# Sheet2.net
KiCad netlist of a schematic drawn in Altium Designer
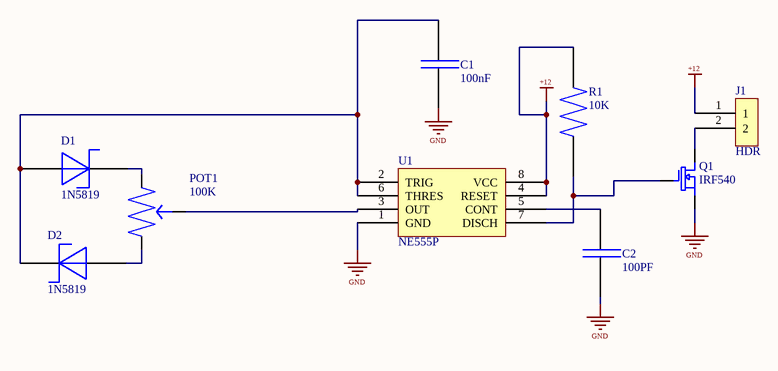
[diagram p0: Sheet2.SchDoc]

(export (version "E")
  (design (tool "Eeschema 10.0.6"))
  (components
    (comp (ref "C1")
      (value "100nF")
      (footprint "CAP")
      (description "Cap Ceramic Monolithic 0.1uF 25VDC 10% Thru-Hole Bulk")
      (fields
        (field (name "MANUFACTURER") "Murata")
        (field (name "MANUFACTURER PART NUMBER") "RCER71E104K0K1H03B")
      )
      (libsource (lib "Schlib2") (part "RCER71E104K0K1H03B"))
    )
    (comp (ref "C2")
      (value "100PF")
      (footprint "CAP")
      (fields
        (field (name "MANUFACTURER") "KEMET")
        (field (name "MANUFACTURER PART NUMBER") "C315C101F3G5TA")
      )
      (libsource (lib "Schlib2") (part "C315C101F3G5TA"))
    )
    (comp (ref "D1")
      (value "1N5819")
      (footprint "DIODE1N5819")
      (description "1N58 Series 600 mV 1 A 40 V Max Reverse Voltage Schottky Barrier Rectifier-DO-41")
      (fields (field (name "MANUFACTURER") "ON Semiconductor / Fairchild"))
      (libsource (lib "Schlib2") (part "1N5819"))
    )
    (comp (ref "D2")
      (value "1N5819")
      (footprint "DIODE1N5819")
      (description "1N58 Series 600 mV 1 A 40 V Max Reverse Voltage Schottky Barrier Rectifier-DO-41")
      (fields (field (name "MANUFACTURER") "ON Semiconductor / Fairchild"))
      (libsource (lib "Schlib2") (part "1N5819"))
    )
    (comp (ref "J1") (value "HDR") (footprint "HDR1X2") (libsource (lib "Schlib2") (part "HDR1X2")))
    (comp (ref "POT1")
      (value "100K")
      (footprint "POT")
      (description "Potentiometers 100K LINEAR 12MM")
      (fields
        (field (name "MANUFACTURER") "Bourns")
        (field (name "MANUFACTURER PART NUMBER") "PDB12-M4251-104BF")
      )
      (libsource (lib "Schlib2") (part "PDB12-M4251-104BF"))
    )
    (comp (ref "Q1")
      (value "IRF540")
      (footprint "TO-220")
      (description "MOSFET N-CH 100V 28A TO-220AB")
      (fields (field (name "MANUFACTURER") "Vishay Siliconix") (field (name "VOLTAGE") "100V"))
      (libsource (lib "Schlib2") (part "IRF540"))
    )
    (comp (ref "R1")
      (value "10K")
      (footprint "TH_L6.8")
      (description "Res Carbon Film 10K Ohm 5% 0.25W(1/4W) -500ppm/C to 350ppm/C Conformal Coated AXL Ammo Pack")
      (fields
        (field (name "MANUFACTURER") "Yageo")
        (field (name "MANUFACTURER PART NUMBER") "CFR-25SJT-52-10K")
      )
      (libsource (lib "Schlib2") (part "CFR-25SJT-52-10K"))
    )
    (comp (ref "U1")
      (value "NE555P")
      (footprint "DIP8")
      (description "Standard Timer Single 8-Pin PDIP Tube")
      (fields (field (name "MANUFACTURER") "Texas Instruments"))
      (libsource (lib "Schlib2") (part "NE555P"))
    )
  )
  (nets
    (net (code "1") (name "+12") (class "Default")
      (node (ref "J1") (pin "1") (pinfunction "1_1") (pintype "passive"))
      (node (ref "R1") (pin "1") (pinfunction "1_1") (pintype "passive"))
      (node (ref "U1") (pin "4") (pinfunction "RESET_4") (pintype "passive"))
      (node (ref "U1") (pin "8") (pinfunction "VCC_8") (pintype "passive"))
    )
    (net (code "2") (name "GND") (class "Default")
      (node (ref "C1") (pin "1") (pinfunction "1_1") (pintype "passive"))
      (node (ref "C2") (pin "1") (pinfunction "1_1") (pintype "passive"))
      (node (ref "Q1") (pin "3") (pinfunction "3_3") (pintype "passive"))
      (node (ref "U1") (pin "1") (pinfunction "GND_1") (pintype "passive"))
    )
    (net (code "3") (name "Net-(D1-Pad2)") (class "Default")
      (node (ref "D1") (pin "2") (pinfunction "2_2") (pintype "passive"))
      (node (ref "POT1") (pin "1") (pinfunction "1_1") (pintype "passive"))
    )
    (net (code "4") (name "Net-(D2-Pad1)") (class "Default")
      (node (ref "D2") (pin "1") (pinfunction "1_1") (pintype "passive"))
      (node (ref "POT1") (pin "2") (pinfunction "2_2") (pintype "passive"))
    )
    (net (code "5") (name "Net-(J1-Pad2)") (class "Default")
      (node (ref "J1") (pin "2") (pinfunction "2_2") (pintype "passive"))
      (node (ref "Q1") (pin "2") (pinfunction "2_2") (pintype "passive"))
    )
    (net (code "6") (name "Net-(U1-CONT)") (class "Default")
      (node (ref "C2") (pin "2") (pinfunction "2_2") (pintype "passive"))
      (node (ref "U1") (pin "5") (pinfunction "CONT_5") (pintype "passive"))
    )
    (net (code "7") (name "Net-(U1-DISCH)") (class "Default")
      (node (ref "Q1") (pin "1") (pinfunction "1_1") (pintype "passive"))
      (node (ref "R1") (pin "2") (pinfunction "2_2") (pintype "passive"))
      (node (ref "U1") (pin "7") (pinfunction "DISCH_7") (pintype "passive"))
    )
    (net (code "8") (name "Net-(U1-OUT)") (class "Default")
      (node (ref "POT1") (pin "3") (pinfunction "3_3") (pintype "passive"))
      (node (ref "U1") (pin "3") (pinfunction "OUT_3") (pintype "passive"))
    )
    (net (code "9") (name "Net-(U1-THRES)") (class "Default")
      (node (ref "C1") (pin "2") (pinfunction "2_2") (pintype "passive"))
      (node (ref "D1") (pin "1") (pinfunction "1_1") (pintype "passive"))
      (node (ref "D2") (pin "2") (pinfunction "2_2") (pintype "passive"))
      (node (ref "U1") (pin "2") (pinfunction "TRIG_2") (pintype "passive"))
      (node (ref "U1") (pin "6") (pinfunction "THRES_6") (pintype "passive"))
    )
  )
)
